# BalEv_AINa_v1_0.net
KiCad netlist of a schematic drawn in Altium Designer
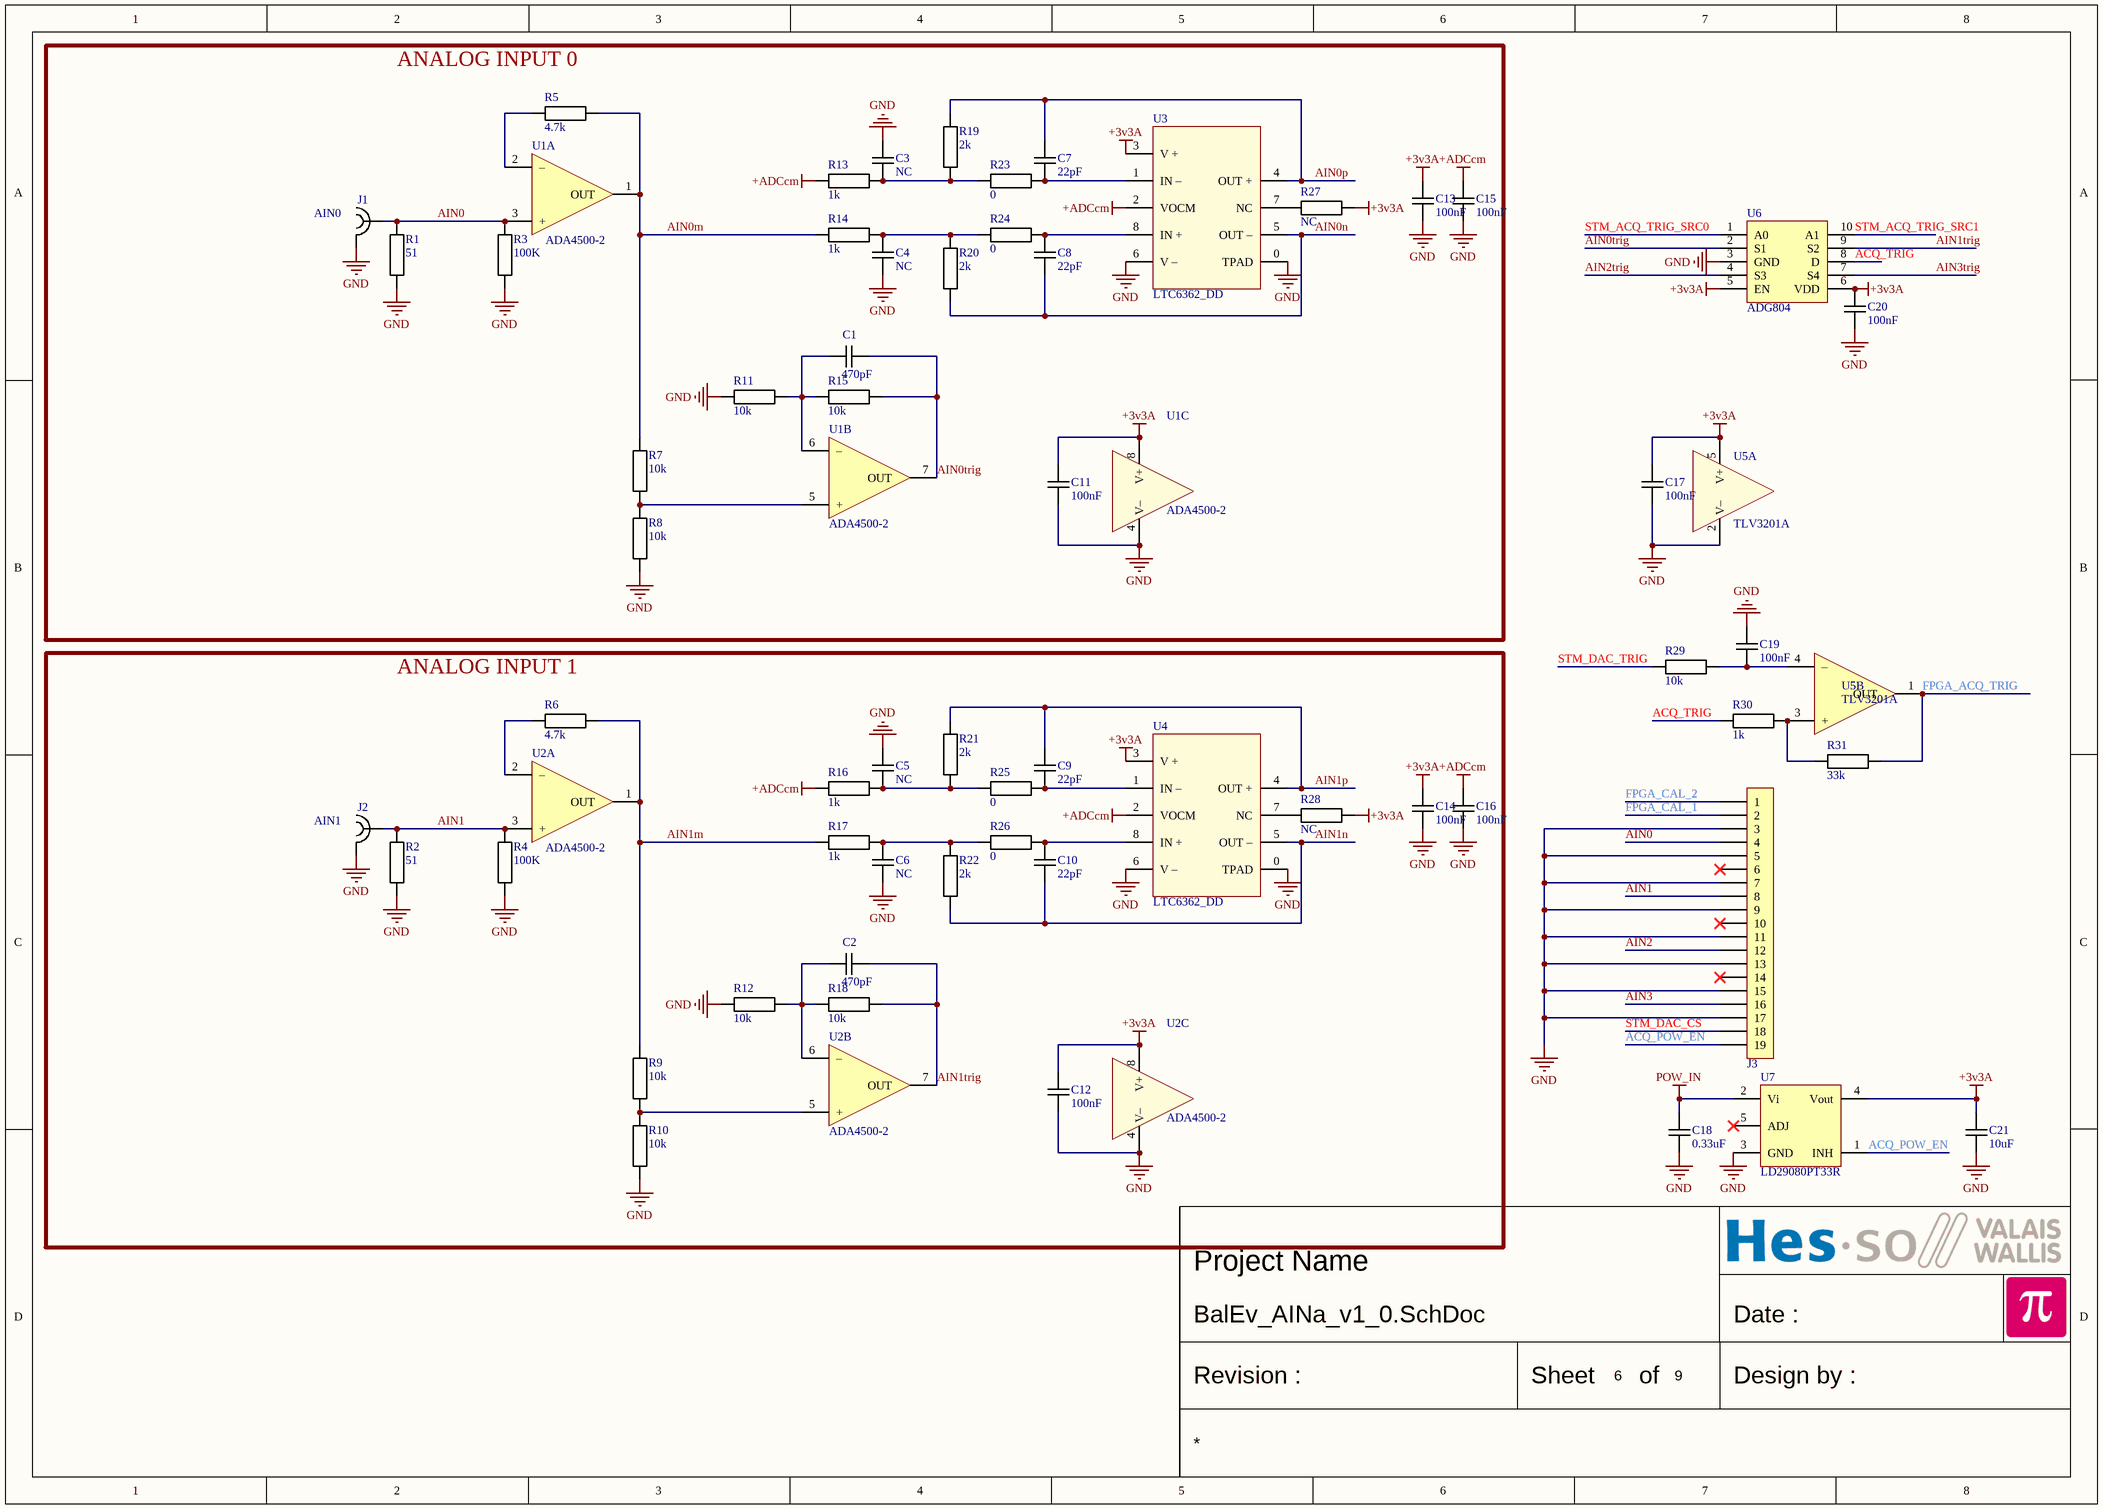
[diagram p0: BalEv_AINa_v1_0.SchDoc]

(export (version "E")
  (design (tool "Eeschema 10.0.6"))
  (components
    (comp (ref "C1")
      (value "470pF")
      (footprint "CAPACITOR 1005 REFLOW")
      (description "Capacitor")
      (libsource (lib "Capacitor") (part "Capacitor"))
    )
    (comp (ref "C2")
      (value "470pF")
      (footprint "CAPACITOR 1005 REFLOW")
      (description "Capacitor")
      (libsource (lib "Capacitor") (part "Capacitor"))
    )
    (comp (ref "C3")
      (value "NC")
      (footprint "CAPACITOR 1005 REFLOW")
      (description "Capacitor")
      (libsource (lib "Capacitor") (part "Capacitor"))
    )
    (comp (ref "C4")
      (value "NC")
      (footprint "CAPACITOR 1005 REFLOW")
      (description "Capacitor")
      (libsource (lib "Capacitor") (part "Capacitor"))
    )
    (comp (ref "C5")
      (value "NC")
      (footprint "CAPACITOR 1005 REFLOW")
      (description "Capacitor")
      (libsource (lib "Capacitor") (part "Capacitor"))
    )
    (comp (ref "C6")
      (value "NC")
      (footprint "CAPACITOR 1005 REFLOW")
      (description "Capacitor")
      (libsource (lib "Capacitor") (part "Capacitor"))
    )
    (comp (ref "C7")
      (value "22pF")
      (footprint "CAPACITOR 1005 REFLOW")
      (description "Capacitor")
      (libsource (lib "Capacitor") (part "Capacitor"))
    )
    (comp (ref "C8")
      (value "22pF")
      (footprint "CAPACITOR 1005 REFLOW")
      (description "Capacitor")
      (libsource (lib "Capacitor") (part "Capacitor"))
    )
    (comp (ref "C9")
      (value "22pF")
      (footprint "CAPACITOR 1005 REFLOW")
      (description "Capacitor")
      (libsource (lib "Capacitor") (part "Capacitor"))
    )
    (comp (ref "C10")
      (value "22pF")
      (footprint "CAPACITOR 1005 REFLOW")
      (description "Capacitor")
      (libsource (lib "Capacitor") (part "Capacitor"))
    )
    (comp (ref "C11")
      (value "100nF")
      (footprint "CAPACITOR 1005 REFLOW")
      (description "Capacitor")
      (libsource (lib "Capacitor") (part "Capacitor"))
    )
    (comp (ref "C12")
      (value "100nF")
      (footprint "CAPACITOR 1005 REFLOW")
      (description "Capacitor")
      (libsource (lib "Capacitor") (part "Capacitor"))
    )
    (comp (ref "C13")
      (value "100nF")
      (footprint "CAPACITOR 1005 REFLOW")
      (description "Capacitor")
      (libsource (lib "Capacitor") (part "Capacitor"))
    )
    (comp (ref "C14")
      (value "100nF")
      (footprint "CAPACITOR 1005 REFLOW")
      (description "Capacitor")
      (libsource (lib "Capacitor") (part "Capacitor"))
    )
    (comp (ref "C15")
      (value "100nF")
      (footprint "CAPACITOR 1005 REFLOW")
      (description "Capacitor")
      (libsource (lib "Capacitor") (part "Capacitor"))
    )
    (comp (ref "C16")
      (value "100nF")
      (footprint "CAPACITOR 1005 REFLOW")
      (description "Capacitor")
      (libsource (lib "Capacitor") (part "Capacitor"))
    )
    (comp (ref "C17")
      (value "100nF")
      (footprint "CAPACITOR 1005 REFLOW")
      (description "Capacitor")
      (libsource (lib "Capacitor") (part "Capacitor"))
    )
    (comp (ref "C18")
      (value "0.33uF")
      (footprint "CAPACITOR 1608 REFLOW")
      (description "Capacitor")
      (libsource (lib "Capacitor") (part "Capacitor"))
    )
    (comp (ref "C19")
      (value "100nF")
      (footprint "CAPACITOR 1005 REFLOW")
      (description "Capacitor")
      (libsource (lib "Capacitor") (part "Capacitor"))
    )
    (comp (ref "C20")
      (value "100nF")
      (footprint "CAPACITOR 1005 REFLOW")
      (description "Capacitor")
      (libsource (lib "Capacitor") (part "Capacitor"))
    )
    (comp (ref "C21")
      (value "10uF")
      (footprint "CAPACITOR 1608 REFLOW")
      (description "Capacitor")
      (libsource (lib "Capacitor") (part "Capacitor"))
    )
    (comp (ref "J1")
      (value "AIN0")
      (footprint "SMA EDGE Molex 732511150")
      (description "SMA EDGE Molex 732511150")
      (libsource (lib "Connector") (part "SMA EDGE Molex 732511150"))
    )
    (comp (ref "J2")
      (value "AIN1")
      (footprint "SMA EDGE Molex 732511150")
      (description "SMA EDGE Molex 732511150")
      (libsource (lib "Connector") (part "SMA EDGE Molex 732511150"))
    )
    (comp (ref "J3")
      (value "NC")
      (footprint "PinHeader1x19 P5.08")
      (description "Plug connector")
      (libsource (lib "PinHeader") (part "PinHeader1x19"))
    )
    (comp (ref "R1")
      (value "51")
      (footprint "RESISTOR 1005 REFLOW")
      (description "Resistor")
      (libsource (lib "Resistor") (part "Resistor"))
    )
    (comp (ref "R2")
      (value "51")
      (footprint "RESISTOR 1005 REFLOW")
      (description "Resistor")
      (libsource (lib "Resistor") (part "Resistor"))
    )
    (comp (ref "R3")
      (value "100K")
      (footprint "RESISTOR 1005 REFLOW")
      (description "Resistor")
      (libsource (lib "Resistor") (part "Resistor"))
    )
    (comp (ref "R4")
      (value "100K")
      (footprint "RESISTOR 1005 REFLOW")
      (description "Resistor")
      (libsource (lib "Resistor") (part "Resistor"))
    )
    (comp (ref "R5")
      (value "4.7k")
      (footprint "RESISTOR 1005 REFLOW")
      (description "Resistor")
      (libsource (lib "Resistor") (part "Resistor"))
    )
    (comp (ref "R6")
      (value "4.7k")
      (footprint "RESISTOR 1005 REFLOW")
      (description "Resistor")
      (libsource (lib "Resistor") (part "Resistor"))
    )
    (comp (ref "R7")
      (value "10k")
      (footprint "RESISTOR 1005 REFLOW")
      (description "Resistor")
      (libsource (lib "Resistor") (part "Resistor"))
    )
    (comp (ref "R8")
      (value "10k")
      (footprint "RESISTOR 1005 REFLOW")
      (description "Resistor")
      (libsource (lib "Resistor") (part "Resistor"))
    )
    (comp (ref "R9")
      (value "10k")
      (footprint "RESISTOR 1005 REFLOW")
      (description "Resistor")
      (libsource (lib "Resistor") (part "Resistor"))
    )
    (comp (ref "R10")
      (value "10k")
      (footprint "RESISTOR 1005 REFLOW")
      (description "Resistor")
      (libsource (lib "Resistor") (part "Resistor"))
    )
    (comp (ref "R11")
      (value "10k")
      (footprint "RESISTOR 1005 REFLOW")
      (description "Resistor")
      (libsource (lib "Resistor") (part "Resistor"))
    )
    (comp (ref "R12")
      (value "10k")
      (footprint "RESISTOR 1005 REFLOW")
      (description "Resistor")
      (libsource (lib "Resistor") (part "Resistor"))
    )
    (comp (ref "R13")
      (value "1k")
      (footprint "RESISTOR 1005 REFLOW")
      (description "Resistor")
      (libsource (lib "Resistor") (part "Resistor"))
    )
    (comp (ref "R14")
      (value "1k")
      (footprint "RESISTOR 1005 REFLOW")
      (description "Resistor")
      (libsource (lib "Resistor") (part "Resistor"))
    )
    (comp (ref "R15")
      (value "10k")
      (footprint "RESISTOR 1005 REFLOW")
      (description "Resistor")
      (libsource (lib "Resistor") (part "Resistor"))
    )
    (comp (ref "R16")
      (value "1k")
      (footprint "RESISTOR 1005 REFLOW")
      (description "Resistor")
      (libsource (lib "Resistor") (part "Resistor"))
    )
    (comp (ref "R17")
      (value "1k")
      (footprint "RESISTOR 1005 REFLOW")
      (description "Resistor")
      (libsource (lib "Resistor") (part "Resistor"))
    )
    (comp (ref "R18")
      (value "10k")
      (footprint "RESISTOR 1005 REFLOW")
      (description "Resistor")
      (libsource (lib "Resistor") (part "Resistor"))
    )
    (comp (ref "R19")
      (value "2k")
      (footprint "RESISTOR 1005 REFLOW")
      (description "Resistor")
      (libsource (lib "Resistor") (part "Resistor"))
    )
    (comp (ref "R20")
      (value "2k")
      (footprint "RESISTOR 1005 REFLOW")
      (description "Resistor")
      (libsource (lib "Resistor") (part "Resistor"))
    )
    (comp (ref "R21")
      (value "2k")
      (footprint "RESISTOR 1005 REFLOW")
      (description "Resistor")
      (libsource (lib "Resistor") (part "Resistor"))
    )
    (comp (ref "R22")
      (value "2k")
      (footprint "RESISTOR 1005 REFLOW")
      (description "Resistor")
      (libsource (lib "Resistor") (part "Resistor"))
    )
    (comp (ref "R23")
      (value "0")
      (footprint "RESISTOR 1005 REFLOW")
      (description "Resistor")
      (libsource (lib "Resistor") (part "Resistor"))
    )
    (comp (ref "R24")
      (value "0")
      (footprint "RESISTOR 1005 REFLOW")
      (description "Resistor")
      (libsource (lib "Resistor") (part "Resistor"))
    )
    (comp (ref "R25")
      (value "0")
      (footprint "RESISTOR 1005 REFLOW")
      (description "Resistor")
      (libsource (lib "Resistor") (part "Resistor"))
    )
    (comp (ref "R26")
      (value "0")
      (footprint "RESISTOR 1005 REFLOW")
      (description "Resistor")
      (libsource (lib "Resistor") (part "Resistor"))
    )
    (comp (ref "R27")
      (value "NC")
      (footprint "RESISTOR 1005 REFLOW")
      (description "Resistor")
      (libsource (lib "Resistor") (part "Resistor"))
    )
    (comp (ref "R28")
      (value "NC")
      (footprint "RESISTOR 1005 REFLOW")
      (description "Resistor")
      (libsource (lib "Resistor") (part "Resistor"))
    )
    (comp (ref "R29")
      (value "10k")
      (footprint "RESISTOR 1005 REFLOW")
      (description "Resistor")
      (libsource (lib "Resistor") (part "Resistor"))
    )
    (comp (ref "R30")
      (value "1k")
      (footprint "RESISTOR 1005 REFLOW")
      (description "Resistor")
      (libsource (lib "Resistor") (part "Resistor"))
    )
    (comp (ref "R31")
      (value "33k")
      (footprint "RESISTOR 1005 REFLOW")
      (description "Resistor")
      (libsource (lib "Resistor") (part "Resistor"))
    )
    (comp (ref "U1")
      (value "ADA4500-2")
      (footprint "MSOP8 P0.65 C3.0X3.0 H1.1")
      (description "Generic dual OPA 8 pins")
      (libsource (lib "Amplifier") (part "OPA DUAL"))
    )
    (comp (ref "U2")
      (value "ADA4500-2")
      (footprint "MSOP8 P0.65 C3.0X3.0 H1.1")
      (description "Generic dual OPA 8 pins")
      (libsource (lib "Amplifier") (part "OPA DUAL"))
    )
    (comp (ref "U3")
      (value "LTC6362_DD")
      (footprint "LFCSP8 P0.5 C3.0x2.8 H1.0")
      (description "IC OPAMP DIFF 410MHZ RRO 8LFCSP")
      (libsource (lib "Amplifier") (part "AD8139ACP"))
    )
    (comp (ref "U4")
      (value "LTC6362_DD")
      (footprint "LFCSP8 P0.5 C3.0x2.8 H1.0")
      (description "IC OPAMP DIFF 410MHZ RRO 8LFCSP")
      (libsource (lib "Amplifier") (part "AD8139ACP"))
    )
    (comp (ref "U5")
      (value "TLV3201A")
      (footprint "SOT23-5 P0.95 C1.6x3.0 H1.3")
      (description "Generic Single Comparator 5pins 1OUT/2-V/3+IN/4-IN/5+V")
      (libsource (lib "Comparator") (part "COMPARATOR SINGLE SOT23-5"))
    )
    (comp (ref "U6")
      (value "ADG804")
      (footprint "TSSOP50P490X110-10N")
      (libsource (lib "ECSlib") (part "ADG804"))
    )
    (comp (ref "U7")
      (value "LD29080PT33R")
      (footprint "TO252-5 P1.27 C6x6.6 H2.4")
      (description "800 mA fixed and adjustable output very low drop voltage regulator")
      (libsource (lib "Regulator") (part "LD29080"))
    )
  )
  (nets
    (net (code "1") (name "+3v3A") (class "Default")
      (node (ref "C11") (pin "1") (pinfunction "1_1") (pintype "passive"))
      (node (ref "C12") (pin "1") (pinfunction "1_1") (pintype "passive"))
      (node (ref "C13") (pin "2") (pinfunction "2_2") (pintype "passive"))
      (node (ref "C14") (pin "2") (pinfunction "2_2") (pintype "passive"))
      (node (ref "C17") (pin "1") (pinfunction "1_1") (pintype "passive"))
      (node (ref "C20") (pin "1") (pinfunction "1_1") (pintype "passive"))
      (node (ref "C21") (pin "2") (pinfunction "2_2") (pintype "passive"))
      (node (ref "R27") (pin "2") (pinfunction "2_2") (pintype "passive"))
      (node (ref "R28") (pin "2") (pinfunction "2_2") (pintype "passive"))
      (node (ref "U1") (pin "8") (pinfunction "V+_8") (pintype "passive"))
      (node (ref "U2") (pin "8") (pinfunction "V+_8") (pintype "passive"))
      (node (ref "U3") (pin "3") (pinfunction "V_+_3") (pintype "passive"))
      (node (ref "U4") (pin "3") (pinfunction "V_+_3") (pintype "passive"))
      (node (ref "U5") (pin "5") (pinfunction "V+_5") (pintype "passive"))
      (node (ref "U6") (pin "5") (pinfunction "EN_5") (pintype "passive"))
      (node (ref "U6") (pin "6") (pinfunction "VDD_6") (pintype "passive"))
      (node (ref "U7") (pin "4") (pinfunction "Vout_4") (pintype "passive"))
    )
    (net (code "2") (name "+ADCcm") (class "Default")
      (node (ref "C15") (pin "2") (pinfunction "2_2") (pintype "passive"))
      (node (ref "C16") (pin "2") (pinfunction "2_2") (pintype "passive"))
      (node (ref "R13") (pin "1") (pinfunction "1_1") (pintype "passive"))
      (node (ref "R16") (pin "1") (pinfunction "1_1") (pintype "passive"))
      (node (ref "U3") (pin "2") (pinfunction "VOCM_2") (pintype "passive"))
      (node (ref "U4") (pin "2") (pinfunction "VOCM_2") (pintype "passive"))
    )
    (net (code "3") (name "/ACQ_POW_EN") (class "Default")
      (node (ref "J3") (pin "19") (pinfunction "19_19") (pintype "passive"))
      (node (ref "U7") (pin "1") (pinfunction "INH_1") (pintype "passive"))
    )
    (net (code "4") (name "/ACQ_TRIG") (class "Default")
      (node (ref "R30") (pin "2") (pinfunction "2_2") (pintype "passive"))
      (node (ref "U6") (pin "8") (pinfunction "D_8") (pintype "passive"))
    )
    (net (code "5") (name "/AIN0") (class "Default")
      (node (ref "J1") (pin "1") (pinfunction "1_1") (pintype "passive"))
      (node (ref "J3") (pin "4") (pinfunction "4_4") (pintype "passive"))
      (node (ref "R1") (pin "2") (pinfunction "2_2") (pintype "passive"))
      (node (ref "R3") (pin "2") (pinfunction "2_2") (pintype "passive"))
      (node (ref "U1") (pin "3") (pinfunction "+_3") (pintype "passive"))
    )
    (net (code "6") (name "/AIN0m") (class "Default")
      (node (ref "R14") (pin "1") (pinfunction "1_1") (pintype "passive"))
      (node (ref "R5") (pin "2") (pinfunction "2_2") (pintype "passive"))
      (node (ref "R7") (pin "1") (pinfunction "1_1") (pintype "passive"))
      (node (ref "U1") (pin "1") (pinfunction "OUT_1") (pintype "passive"))
    )
    (net (code "7") (name "/AIN0n") (class "Default")
      (node (ref "C8") (pin "1") (pinfunction "1_1") (pintype "passive"))
      (node (ref "R20") (pin "2") (pinfunction "2_2") (pintype "passive"))
      (node (ref "U3") (pin "5") (pinfunction "OUT_–_5") (pintype "passive"))
    )
    (net (code "8") (name "/AIN0p") (class "Default")
      (node (ref "C7") (pin "1") (pinfunction "1_1") (pintype "passive"))
      (node (ref "R19") (pin "2") (pinfunction "2_2") (pintype "passive"))
      (node (ref "U3") (pin "4") (pinfunction "OUT_+_4") (pintype "passive"))
    )
    (net (code "9") (name "/AIN0trig") (class "Default")
      (node (ref "C1") (pin "1") (pinfunction "1_1") (pintype "passive"))
      (node (ref "R15") (pin "2") (pinfunction "2_2") (pintype "passive"))
      (node (ref "U1") (pin "7") (pinfunction "OUT_7") (pintype "passive"))
      (node (ref "U6") (pin "2") (pinfunction "S1_2") (pintype "passive"))
    )
    (net (code "10") (name "/AIN1") (class "Default")
      (node (ref "J2") (pin "1") (pinfunction "1_1") (pintype "passive"))
      (node (ref "J3") (pin "8") (pinfunction "8_8") (pintype "passive"))
      (node (ref "R2") (pin "2") (pinfunction "2_2") (pintype "passive"))
      (node (ref "R4") (pin "2") (pinfunction "2_2") (pintype "passive"))
      (node (ref "U2") (pin "3") (pinfunction "+_3") (pintype "passive"))
    )
    (net (code "11") (name "/AIN1m") (class "Default")
      (node (ref "R17") (pin "1") (pinfunction "1_1") (pintype "passive"))
      (node (ref "R6") (pin "2") (pinfunction "2_2") (pintype "passive"))
      (node (ref "R9") (pin "1") (pinfunction "1_1") (pintype "passive"))
      (node (ref "U2") (pin "1") (pinfunction "OUT_1") (pintype "passive"))
    )
    (net (code "12") (name "/AIN1n") (class "Default")
      (node (ref "C10") (pin "1") (pinfunction "1_1") (pintype "passive"))
      (node (ref "R22") (pin "2") (pinfunction "2_2") (pintype "passive"))
      (node (ref "U4") (pin "5") (pinfunction "OUT_–_5") (pintype "passive"))
    )
    (net (code "13") (name "/AIN1p") (class "Default")
      (node (ref "C9") (pin "1") (pinfunction "1_1") (pintype "passive"))
      (node (ref "R21") (pin "2") (pinfunction "2_2") (pintype "passive"))
      (node (ref "U4") (pin "4") (pinfunction "OUT_+_4") (pintype "passive"))
    )
    (net (code "14") (name "/AIN1trig") (class "Default")
      (node (ref "C2") (pin "1") (pinfunction "1_1") (pintype "passive"))
      (node (ref "R18") (pin "2") (pinfunction "2_2") (pintype "passive"))
      (node (ref "U2") (pin "7") (pinfunction "OUT_7") (pintype "passive"))
      (node (ref "U6") (pin "9") (pinfunction "S2_9") (pintype "passive"))
    )
    (net (code "15") (name "/AIN2") (class "Default")
      (node (ref "J3") (pin "12") (pinfunction "12_12") (pintype "passive"))
    )
    (net (code "16") (name "/AIN2trig") (class "Default")
      (node (ref "U6") (pin "4") (pinfunction "S3_4") (pintype "passive"))
    )
    (net (code "17") (name "/AIN3") (class "Default")
      (node (ref "J3") (pin "16") (pinfunction "16_16") (pintype "passive"))
    )
    (net (code "18") (name "/AIN3trig") (class "Default")
      (node (ref "U6") (pin "7") (pinfunction "S4_7") (pintype "passive"))
    )
    (net (code "19") (name "/FPGA_ACQ_TRIG") (class "Default")
      (node (ref "R31") (pin "1") (pinfunction "1_1") (pintype "passive"))
      (node (ref "U5") (pin "1") (pinfunction "OUT_1") (pintype "passive"))
    )
    (net (code "20") (name "/FPGA_CAL_1") (class "Default")
      (node (ref "J3") (pin "2") (pinfunction "2_2") (pintype "passive"))
    )
    (net (code "21") (name "/FPGA_CAL_2") (class "Default")
      (node (ref "J3") (pin "1") (pinfunction "1_1") (pintype "passive"))
    )
    (net (code "22") (name "/STM_ACQ_TRIG_SRC0") (class "Default")
      (node (ref "U6") (pin "1") (pinfunction "A0_1") (pintype "passive"))
    )
    (net (code "23") (name "/STM_ACQ_TRIG_SRC1") (class "Default")
      (node (ref "U6") (pin "10") (pinfunction "A1_10") (pintype "passive"))
    )
    (net (code "24") (name "/STM_DAC_CS") (class "Default")
      (node (ref "J3") (pin "18") (pinfunction "18_18") (pintype "passive"))
    )
    (net (code "25") (name "/STM_DAC_TRIG") (class "Default")
      (node (ref "R29") (pin "2") (pinfunction "2_2") (pintype "passive"))
    )
    (net (code "26") (name "GND") (class "Default")
      (node (ref "C11") (pin "2") (pinfunction "2_2") (pintype "passive"))
      (node (ref "C12") (pin "2") (pinfunction "2_2") (pintype "passive"))
      (node (ref "C13") (pin "1") (pinfunction "1_1") (pintype "passive"))
      (node (ref "C14") (pin "1") (pinfunction "1_1") (pintype "passive"))
      (node (ref "C15") (pin "1") (pinfunction "1_1") (pintype "passive"))
      (node (ref "C16") (pin "1") (pinfunction "1_1") (pintype "passive"))
      (node (ref "C17") (pin "2") (pinfunction "2_2") (pintype "passive"))
      (node (ref "C18") (pin "1") (pinfunction "1_1") (pintype "passive"))
      (node (ref "C19") (pin "1") (pinfunction "1_1") (pintype "passive"))
      (node (ref "C20") (pin "2") (pinfunction "2_2") (pintype "passive"))
      (node (ref "C21") (pin "1") (pinfunction "1_1") (pintype "passive"))
      (node (ref "C3") (pin "1") (pinfunction "1_1") (pintype "passive"))
      (node (ref "C4") (pin "2") (pinfunction "2_2") (pintype "passive"))
      (node (ref "C5") (pin "1") (pinfunction "1_1") (pintype "passive"))
      (node (ref "C6") (pin "2") (pinfunction "2_2") (pintype "passive"))
      (node (ref "J1") (pin "2") (pinfunction "2_2") (pintype "passive"))
      (node (ref "J2") (pin "2") (pinfunction "2_2") (pintype "passive"))
      (node (ref "J3") (pin "11") (pinfunction "11_11") (pintype "passive"))
      (node (ref "J3") (pin "13") (pinfunction "13_13") (pintype "passive"))
      (node (ref "J3") (pin "15") (pinfunction "15_15") (pintype "passive"))
      (node (ref "J3") (pin "17") (pinfunction "17_17") (pintype "passive"))
      (node (ref "J3") (pin "3") (pinfunction "3_3") (pintype "passive"))
      (node (ref "J3") (pin "5") (pinfunction "5_5") (pintype "passive"))
      (node (ref "J3") (pin "7") (pinfunction "7_7") (pintype "passive"))
      (node (ref "J3") (pin "9") (pinfunction "9_9") (pintype "passive"))
      (node (ref "R1") (pin "1") (pinfunction "1_1") (pintype "passive"))
      (node (ref "R10") (pin "2") (pinfunction "2_2") (pintype "passive"))
      (node (ref "R11") (pin "1") (pinfunction "1_1") (pintype "passive"))
      (node (ref "R12") (pin "1") (pinfunction "1_1") (pintype "passive"))
      (node (ref "R2") (pin "1") (pinfunction "1_1") (pintype "passive"))
      (node (ref "R3") (pin "1") (pinfunction "1_1") (pintype "passive"))
      (node (ref "R4") (pin "1") (pinfunction "1_1") (pintype "passive"))
      (node (ref "R8") (pin "2") (pinfunction "2_2") (pintype "passive"))
      (node (ref "U1") (pin "4") (pinfunction "V–_4") (pintype "passive"))
      (node (ref "U2") (pin "4") (pinfunction "V–_4") (pintype "passive"))
      (node (ref "U3") (pin "0") (pinfunction "TPAD_0") (pintype "passive"))
      (node (ref "U3") (pin "6") (pinfunction "V_–_6") (pintype "passive"))
      (node (ref "U4") (pin "0") (pinfunction "TPAD_0") (pintype "passive"))
      (node (ref "U4") (pin "6") (pinfunction "V_–_6") (pintype "passive"))
      (node (ref "U5") (pin "2") (pinfunction "V–_2") (pintype "passive"))
      (node (ref "U6") (pin "3") (pinfunction "GND_3") (pintype "passive"))
      (node (ref "U7") (pin "3") (pinfunction "GND_3") (pintype "passive"))
    )
    (net (code "27") (name "Net-(C3-Pad2)") (class "Default")
      (node (ref "C3") (pin "2") (pinfunction "2_2") (pintype "passive"))
      (node (ref "R13") (pin "2") (pinfunction "2_2") (pintype "passive"))
      (node (ref "R19") (pin "1") (pinfunction "1_1") (pintype "passive"))
      (node (ref "R23") (pin "2") (pinfunction "2_2") (pintype "passive"))
    )
    (net (code "28") (name "Net-(C4-Pad1)") (class "Default")
      (node (ref "C4") (pin "1") (pinfunction "1_1") (pintype "passive"))
      (node (ref "R14") (pin "2") (pinfunction "2_2") (pintype "passive"))
      (node (ref "R20") (pin "1") (pinfunction "1_1") (pintype "passive"))
      (node (ref "R24") (pin "1") (pinfunction "1_1") (pintype "passive"))
    )
    (net (code "29") (name "Net-(C5-Pad2)") (class "Default")
      (node (ref "C5") (pin "2") (pinfunction "2_2") (pintype "passive"))
      (node (ref "R16") (pin "2") (pinfunction "2_2") (pintype "passive"))
      (node (ref "R21") (pin "1") (pinfunction "1_1") (pintype "passive"))
      (node (ref "R25") (pin "2") (pinfunction "2_2") (pintype "passive"))
    )
    (net (code "30") (name "Net-(C6-Pad1)") (class "Default")
      (node (ref "C6") (pin "1") (pinfunction "1_1") (pintype "passive"))
      (node (ref "R17") (pin "2") (pinfunction "2_2") (pintype "passive"))
      (node (ref "R22") (pin "1") (pinfunction "1_1") (pintype "passive"))
      (node (ref "R26") (pin "1") (pinfunction "1_1") (pintype "passive"))
    )
    (net (code "31") (name "Net-(U1A-–)") (class "Default")
      (node (ref "R5") (pin "1") (pinfunction "1_1") (pintype "passive"))
      (node (ref "U1") (pin "2") (pinfunction "–_2") (pintype "passive"))
    )
    (net (code "32") (name "Net-(U1B-+)") (class "Default")
      (node (ref "R7") (pin "2") (pinfunction "2_2") (pintype "passive"))
      (node (ref "R8") (pin "1") (pinfunction "1_1") (pintype "passive"))
      (node (ref "U1") (pin "5") (pinfunction "+_5") (pintype "passive"))
    )
    (net (code "33") (name "Net-(U1B-–)") (class "Default")
      (node (ref "C1") (pin "2") (pinfunction "2_2") (pintype "passive"))
      (node (ref "R11") (pin "2") (pinfunction "2_2") (pintype "passive"))
      (node (ref "R15") (pin "1") (pinfunction "1_1") (pintype "passive"))
      (node (ref "U1") (pin "6") (pinfunction "–_6") (pintype "passive"))
    )
    (net (code "34") (name "Net-(U2A-–)") (class "Default")
      (node (ref "R6") (pin "1") (pinfunction "1_1") (pintype "passive"))
      (node (ref "U2") (pin "2") (pinfunction "–_2") (pintype "passive"))
    )
    (net (code "35") (name "Net-(U2B-+)") (class "Default")
      (node (ref "R10") (pin "1") (pinfunction "1_1") (pintype "passive"))
      (node (ref "R9") (pin "2") (pinfunction "2_2") (pintype "passive"))
      (node (ref "U2") (pin "5") (pinfunction "+_5") (pintype "passive"))
    )
    (net (code "36") (name "Net-(U2B-–)") (class "Default")
      (node (ref "C2") (pin "2") (pinfunction "2_2") (pintype "passive"))
      (node (ref "R12") (pin "2") (pinfunction "2_2") (pintype "passive"))
      (node (ref "R18") (pin "1") (pinfunction "1_1") (pintype "passive"))
      (node (ref "U2") (pin "6") (pinfunction "–_6") (pintype "passive"))
    )
    (net (code "37") (name "Net-(U3-IN_+)") (class "Default")
      (node (ref "C8") (pin "2") (pinfunction "2_2") (pintype "passive"))
      (node (ref "R24") (pin "2") (pinfunction "2_2") (pintype "passive"))
      (node (ref "U3") (pin "8") (pinfunction "IN_+_8") (pintype "passive"))
    )
    (net (code "38") (name "Net-(U3-IN_–)") (class "Default")
      (node (ref "C7") (pin "2") (pinfunction "2_2") (pintype "passive"))
      (node (ref "R23") (pin "1") (pinfunction "1_1") (pintype "passive"))
      (node (ref "U3") (pin "1") (pinfunction "IN_–_1") (pintype "passive"))
    )
    (net (code "39") (name "Net-(U3-NC)") (class "Default")
      (node (ref "R27") (pin "1") (pinfunction "1_1") (pintype "passive"))
      (node (ref "U3") (pin "7") (pinfunction "NC_7") (pintype "passive"))
    )
    (net (code "40") (name "Net-(U4-IN_+)") (class "Default")
      (node (ref "C10") (pin "2") (pinfunction "2_2") (pintype "passive"))
      (node (ref "R26") (pin "2") (pinfunction "2_2") (pintype "passive"))
      (node (ref "U4") (pin "8") (pinfunction "IN_+_8") (pintype "passive"))
    )
    (net (code "41") (name "Net-(U4-IN_–)") (class "Default")
      (node (ref "C9") (pin "2") (pinfunction "2_2") (pintype "passive"))
      (node (ref "R25") (pin "1") (pinfunction "1_1") (pintype "passive"))
      (node (ref "U4") (pin "1") (pinfunction "IN_–_1") (pintype "passive"))
    )
    (net (code "42") (name "Net-(U4-NC)") (class "Default")
      (node (ref "R28") (pin "1") (pinfunction "1_1") (pintype "passive"))
      (node (ref "U4") (pin "7") (pinfunction "NC_7") (pintype "passive"))
    )
    (net (code "43") (name "Net-(U5B-+)") (class "Default")
      (node (ref "R30") (pin "1") (pinfunction "1_1") (pintype "passive"))
      (node (ref "R31") (pin "2") (pinfunction "2_2") (pintype "passive"))
      (node (ref "U5") (pin "3") (pinfunction "+_3") (pintype "passive"))
    )
    (net (code "44") (name "Net-(U5B-–)") (class "Default")
      (node (ref "C19") (pin "2") (pinfunction "2_2") (pintype "passive"))
      (node (ref "R29") (pin "1") (pinfunction "1_1") (pintype "passive"))
      (node (ref "U5") (pin "4") (pinfunction "–_4") (pintype "passive"))
    )
    (net (code "45") (name "POW_IN") (class "Default")
      (node (ref "C18") (pin "2") (pinfunction "2_2") (pintype "passive"))
      (node (ref "U7") (pin "2") (pinfunction "Vi_2") (pintype "passive"))
    )
    (net (code "46") (name "unconnected-(J3-Pad6)") (class "Default")
      (node (ref "J3") (pin "6") (pinfunction "6_6") (pintype "passive+no_connect"))
    )
    (net (code "47") (name "unconnected-(J3-Pad10)") (class "Default")
      (node (ref "J3") (pin "10") (pinfunction "10_10") (pintype "passive+no_connect"))
    )
    (net (code "48") (name "unconnected-(J3-Pad14)") (class "Default")
      (node (ref "J3") (pin "14") (pinfunction "14_14") (pintype "passive+no_connect"))
    )
    (net (code "49") (name "unconnected-(U7-ADJ-Pad5)") (class "Default")
      (node (ref "U7") (pin "5") (pinfunction "ADJ_5") (pintype "passive+no_connect"))
    )
  )
)
